# M710H.net
KiCad netlist of a schematic drawn in EAGLE
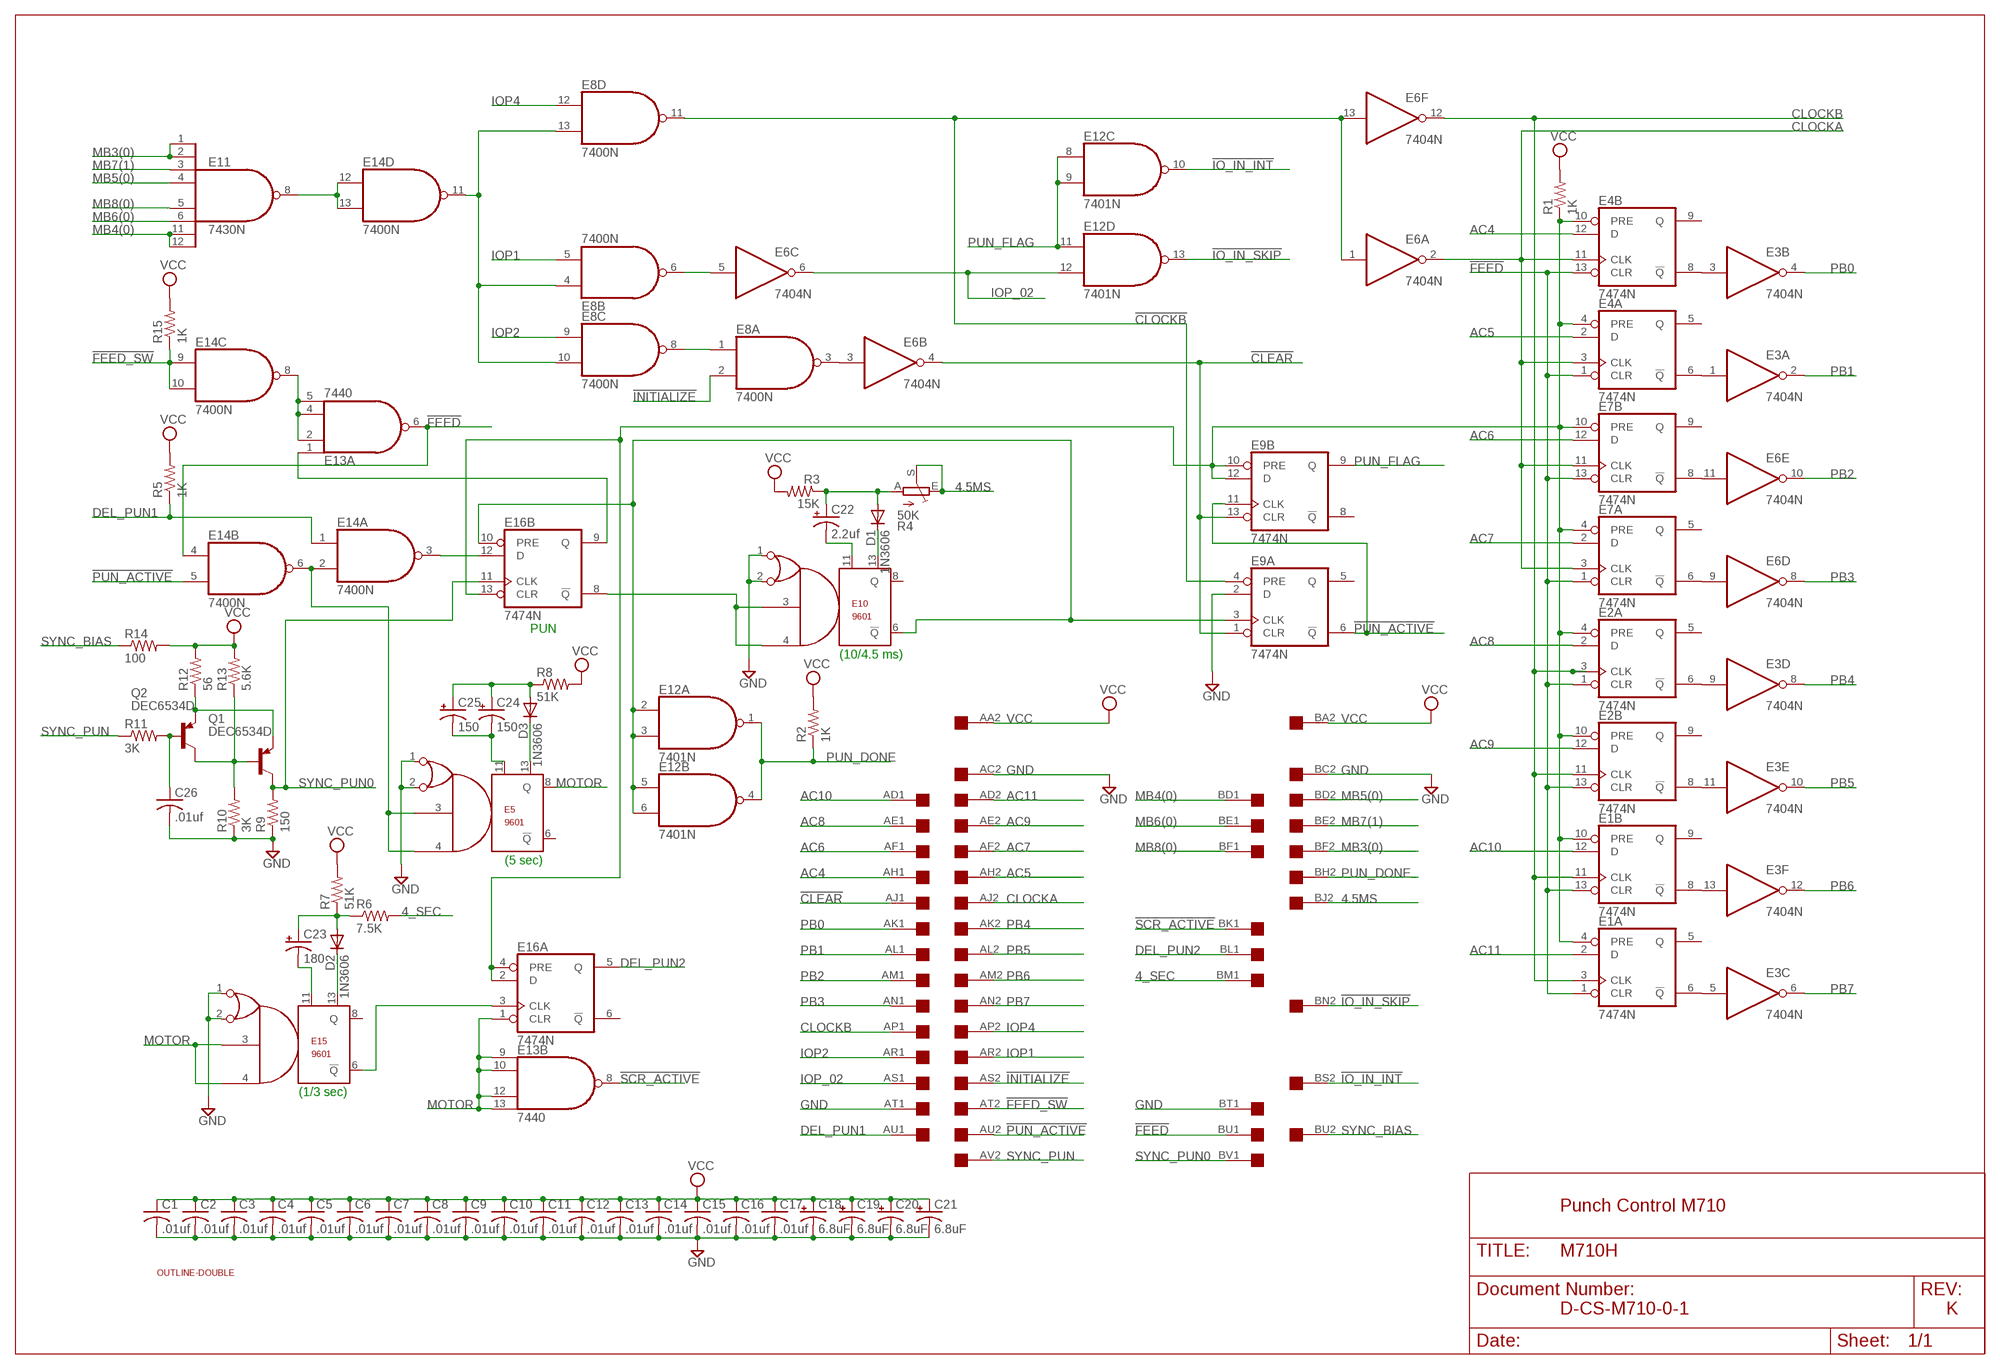
[diagram p0: schematic, sheet 1]

(export (version "E")
  (design (tool "Eeschema 10.0.6"))
  (components
    (comp (ref "C1")
      (value ".01uf")
      (footprint "eagle-import:C050-025X075")
      (libsource (lib "eagle-import") (part "C-US050-025X075"))
    )
    (comp (ref "C2")
      (value ".01uf")
      (footprint "eagle-import:C050-025X075")
      (libsource (lib "eagle-import") (part "C-US050-025X075"))
    )
    (comp (ref "C3")
      (value ".01uf")
      (footprint "eagle-import:C050-025X075")
      (libsource (lib "eagle-import") (part "C-US050-025X075"))
    )
    (comp (ref "C4")
      (value ".01uf")
      (footprint "eagle-import:C050-025X075")
      (libsource (lib "eagle-import") (part "C-US050-025X075"))
    )
    (comp (ref "C5")
      (value ".01uf")
      (footprint "eagle-import:C050-025X075")
      (libsource (lib "eagle-import") (part "C-US050-025X075"))
    )
    (comp (ref "C6")
      (value ".01uf")
      (footprint "eagle-import:C050-025X075")
      (libsource (lib "eagle-import") (part "C-US050-025X075"))
    )
    (comp (ref "C7")
      (value ".01uf")
      (footprint "eagle-import:C050-025X075")
      (libsource (lib "eagle-import") (part "C-US050-025X075"))
    )
    (comp (ref "C8")
      (value ".01uf")
      (footprint "eagle-import:C050-025X075")
      (libsource (lib "eagle-import") (part "C-US050-025X075"))
    )
    (comp (ref "C9")
      (value ".01uf")
      (footprint "eagle-import:C050-025X075")
      (libsource (lib "eagle-import") (part "C-US050-025X075"))
    )
    (comp (ref "C10")
      (value ".01uf")
      (footprint "eagle-import:C050-025X075")
      (libsource (lib "eagle-import") (part "C-US050-025X075"))
    )
    (comp (ref "C11")
      (value ".01uf")
      (footprint "eagle-import:C050-025X075")
      (libsource (lib "eagle-import") (part "C-US050-025X075"))
    )
    (comp (ref "C12")
      (value ".01uf")
      (footprint "eagle-import:C050-025X075")
      (libsource (lib "eagle-import") (part "C-US050-025X075"))
    )
    (comp (ref "C13")
      (value ".01uf")
      (footprint "eagle-import:C050-025X075")
      (libsource (lib "eagle-import") (part "C-US050-025X075"))
    )
    (comp (ref "C14")
      (value ".01uf")
      (footprint "eagle-import:C050-025X075")
      (libsource (lib "eagle-import") (part "C-US050-025X075"))
    )
    (comp (ref "C15")
      (value ".01uf")
      (footprint "eagle-import:C050-025X075")
      (libsource (lib "eagle-import") (part "C-US050-025X075"))
    )
    (comp (ref "C16")
      (value ".01uf")
      (footprint "eagle-import:C050-025X075")
      (libsource (lib "eagle-import") (part "C-US050-025X075"))
    )
    (comp (ref "C17")
      (value ".01uf")
      (footprint "eagle-import:C050-025X075")
      (libsource (lib "eagle-import") (part "C-US050-025X075"))
    )
    (comp (ref "C18")
      (value "6.8uF")
      (footprint "eagle-import:E12-8")
      (libsource (lib "eagle-import") (part "CPOL-USE20-8AXIAL"))
    )
    (comp (ref "C19")
      (value "6.8uF")
      (footprint "eagle-import:E12-8")
      (libsource (lib "eagle-import") (part "CPOL-USE20-8AXIAL"))
    )
    (comp (ref "C20")
      (value "6.8uF")
      (footprint "eagle-import:E12-8")
      (libsource (lib "eagle-import") (part "CPOL-USE20-8AXIAL"))
    )
    (comp (ref "C21")
      (value "6.8uF")
      (footprint "eagle-import:E12-8")
      (libsource (lib "eagle-import") (part "CPOL-USE20-8AXIAL"))
    )
    (comp (ref "C22")
      (value "2.2uf")
      (footprint "eagle-import:E15-5")
      (libsource (lib "eagle-import") (part "CPOL-USE15-5AXIAL"))
    )
    (comp (ref "C23")
      (value "180")
      (footprint "eagle-import:E12-8")
      (libsource (lib "eagle-import") (part "CPOL-USE20-8AXIAL"))
    )
    (comp (ref "C24")
      (value "150")
      (footprint "eagle-import:E22-6")
      (libsource (lib "eagle-import") (part "CPOL-USE22-6AXIAL"))
    )
    (comp (ref "C25")
      (value "150")
      (footprint "eagle-import:E22-6")
      (libsource (lib "eagle-import") (part "CPOL-USE22-6AXIAL"))
    )
    (comp (ref "C26")
      (value ".01uf")
      (footprint "eagle-import:C050-025X075")
      (libsource (lib "eagle-import") (part "C-US050-025X075"))
    )
    (comp (ref "D1")
      (value "1N3606")
      (footprint "eagle-import:DO41-10")
      (libsource (lib "eagle-import") (part "1N4004"))
    )
    (comp (ref "D2")
      (value "1N3606")
      (footprint "eagle-import:DO41-10")
      (libsource (lib "eagle-import") (part "1N4004"))
    )
    (comp (ref "D3")
      (value "1N3606")
      (footprint "eagle-import:DO41-10")
      (libsource (lib "eagle-import") (part "1N4004"))
    )
    (comp (ref "E1")
      (value "7474N")
      (footprint "eagle-import:DIL14")
      (libsource (lib "eagle-import") (part "7474NS"))
    )
    (comp (ref "E2")
      (value "7474N")
      (footprint "eagle-import:DIL14")
      (libsource (lib "eagle-import") (part "7474NS"))
    )
    (comp (ref "E3")
      (value "7404N")
      (footprint "eagle-import:DIL14")
      (libsource (lib "eagle-import") (part "7404N"))
    )
    (comp (ref "E4")
      (value "7474N")
      (footprint "eagle-import:DIL14")
      (libsource (lib "eagle-import") (part "7474NS"))
    )
    (comp (ref "E5")
      (value "9601")
      (footprint "eagle-import:DIL14")
      (libsource (lib "eagle-import") (part "9601"))
    )
    (comp (ref "E6")
      (value "7404N")
      (footprint "eagle-import:DIL14")
      (libsource (lib "eagle-import") (part "7404N"))
    )
    (comp (ref "E7")
      (value "7474N")
      (footprint "eagle-import:DIL14")
      (libsource (lib "eagle-import") (part "7474NS"))
    )
    (comp (ref "E8")
      (value "7400N")
      (footprint "eagle-import:DIL14")
      (libsource (lib "eagle-import") (part "7400N"))
    )
    (comp (ref "E9")
      (value "7474N")
      (footprint "eagle-import:DIL14")
      (libsource (lib "eagle-import") (part "7474NS"))
    )
    (comp (ref "E10")
      (value "9601")
      (footprint "eagle-import:DIL14")
      (libsource (lib "eagle-import") (part "9601"))
    )
    (comp (ref "E11")
      (value "7430N")
      (footprint "eagle-import:DIL14")
      (libsource (lib "eagle-import") (part "7430N"))
    )
    (comp (ref "E12")
      (value "7401N")
      (footprint "eagle-import:DIL14")
      (libsource (lib "eagle-import") (part "7401NLS"))
    )
    (comp (ref "E13")
      (value "7440")
      (footprint "eagle-import:DIL14")
      (libsource (lib "eagle-import") (part "7420NS"))
    )
    (comp (ref "E14")
      (value "7400N")
      (footprint "eagle-import:DIL14")
      (libsource (lib "eagle-import") (part "7400N"))
    )
    (comp (ref "E15")
      (value "9601")
      (footprint "eagle-import:DIL14")
      (libsource (lib "eagle-import") (part "9601"))
    )
    (comp (ref "E16")
      (value "7474N")
      (footprint "eagle-import:DIL14")
      (libsource (lib "eagle-import") (part "7474NS"))
    )
    (comp (ref "Q1")
      (value "DEC6534D")
      (footprint "eagle-import:TO5")
      (libsource (lib "eagle-import") (part "2N2905"))
    )
    (comp (ref "Q2")
      (value "DEC6534D")
      (footprint "eagle-import:TO5")
      (libsource (lib "eagle-import") (part "2N2905"))
    )
    (comp (ref "R1")
      (value "1K")
      (footprint "eagle-import:0207_10")
      (libsource (lib "eagle-import") (part "R-US_0207/10"))
    )
    (comp (ref "R2")
      (value "1K")
      (footprint "eagle-import:0207_10")
      (libsource (lib "eagle-import") (part "R-US_0207/10"))
    )
    (comp (ref "R3")
      (value "15K")
      (footprint "eagle-import:0207_10")
      (libsource (lib "eagle-import") (part "R-US_0207/10"))
    )
    (comp (ref "R4")
      (value "50K")
      (footprint "eagle-import:RJ6")
      (libsource (lib "eagle-import") (part "TRIM_EU-RJ6"))
    )
    (comp (ref "R5")
      (value "1K")
      (footprint "eagle-import:0207_10")
      (libsource (lib "eagle-import") (part "R-US_0207/10"))
    )
    (comp (ref "R6")
      (value "7.5K")
      (footprint "eagle-import:0207_10")
      (libsource (lib "eagle-import") (part "R-US_0207/10"))
    )
    (comp (ref "R7")
      (value "51K")
      (footprint "eagle-import:0207_10")
      (libsource (lib "eagle-import") (part "R-US_0207/10"))
    )
    (comp (ref "R8")
      (value "51K")
      (footprint "eagle-import:0207_10")
      (libsource (lib "eagle-import") (part "R-US_0207/10"))
    )
    (comp (ref "R9")
      (value "150")
      (footprint "eagle-import:0207_10")
      (libsource (lib "eagle-import") (part "R-US_0207/10"))
    )
    (comp (ref "R10")
      (value "3K")
      (footprint "eagle-import:0207_10")
      (libsource (lib "eagle-import") (part "R-US_0207/10"))
    )
    (comp (ref "R11")
      (value "3K")
      (footprint "eagle-import:0207_10")
      (libsource (lib "eagle-import") (part "R-US_0207/10"))
    )
    (comp (ref "R12")
      (value "56")
      (footprint "eagle-import:0207_10")
      (libsource (lib "eagle-import") (part "R-US_0207/10"))
    )
    (comp (ref "R13")
      (value "5.6K")
      (footprint "eagle-import:0207_10")
      (libsource (lib "eagle-import") (part "R-US_0207/10"))
    )
    (comp (ref "R14")
      (value "100")
      (footprint "eagle-import:0207_10")
      (libsource (lib "eagle-import") (part "R-US_0207/10"))
    )
    (comp (ref "R15")
      (value "1K")
      (footprint "eagle-import:0207_10")
      (libsource (lib "eagle-import") (part "R-US_0207/10"))
    )
    (comp (ref "U$1")
      (value "OUTLINE-DOUBLE")
      (footprint "eagle-import:DOUBLE")
      (libsource (lib "eagle-import") (part "OUTLINE-DOUBLE"))
    )
    (comp (ref "U$2")
      (value "DOUBLE")
      (footprint "eagle-import:EDGE-CON4")
      (libsource (lib "eagle-import") (part "DOUBLE"))
    )
  )
  (nets
    (net (code "1") (name "/4.5MS") (class "Default")
      (node (ref "R4") (pin "E") (pinfunction "E_E") (pintype "passive"))
      (node (ref "R4") (pin "S") (pinfunction "S_S") (pintype "passive"))
      (node (ref "U$2") (pin "BJ2") (pinfunction "1_BJ2") (pintype "bidirectional"))
    )
    (net (code "2") (name "/4_SEC") (class "Default")
      (node (ref "R6") (pin "2") (pinfunction "2_2") (pintype "passive"))
      (node (ref "U$2") (pin "BM1") (pinfunction "1_BM1") (pintype "bidirectional"))
    )
    (net (code "3") (name "/AC4") (class "Default")
      (node (ref "E4") (pin "12") (pinfunction "D_12") (pintype "input"))
      (node (ref "U$2") (pin "AH1") (pinfunction "1_AH1") (pintype "bidirectional"))
    )
    (net (code "4") (name "/AC5") (class "Default")
      (node (ref "E4") (pin "2") (pinfunction "D_2") (pintype "input"))
      (node (ref "U$2") (pin "AH2") (pinfunction "1_AH2") (pintype "bidirectional"))
    )
    (net (code "5") (name "/AC6") (class "Default")
      (node (ref "E7") (pin "12") (pinfunction "D_12") (pintype "input"))
      (node (ref "U$2") (pin "AF1") (pinfunction "1_AF1") (pintype "bidirectional"))
    )
    (net (code "6") (name "/AC7") (class "Default")
      (node (ref "E7") (pin "2") (pinfunction "D_2") (pintype "input"))
      (node (ref "U$2") (pin "AF2") (pinfunction "1_AF2") (pintype "bidirectional"))
    )
    (net (code "7") (name "/AC8") (class "Default")
      (node (ref "E2") (pin "2") (pinfunction "D_2") (pintype "input"))
      (node (ref "U$2") (pin "AE1") (pinfunction "1_AE1") (pintype "bidirectional"))
    )
    (net (code "8") (name "/AC9") (class "Default")
      (node (ref "E2") (pin "12") (pinfunction "D_12") (pintype "input"))
      (node (ref "U$2") (pin "AE2") (pinfunction "1_AE2") (pintype "bidirectional"))
    )
    (net (code "9") (name "/AC10") (class "Default")
      (node (ref "E1") (pin "12") (pinfunction "D_12") (pintype "input"))
      (node (ref "U$2") (pin "AD1") (pinfunction "1_AD1") (pintype "bidirectional"))
    )
    (net (code "10") (name "/AC11") (class "Default")
      (node (ref "E1") (pin "2") (pinfunction "D_2") (pintype "input"))
      (node (ref "U$2") (pin "AD2") (pinfunction "1_AD2") (pintype "bidirectional"))
    )
    (net (code "11") (name "/CLOCKA") (class "Default")
      (node (ref "E4") (pin "11") (pinfunction "CLK_11") (pintype "input"))
      (node (ref "E4") (pin "3") (pinfunction "CLK_3") (pintype "input"))
      (node (ref "E6") (pin "2") (pinfunction "O_2") (pintype "output"))
      (node (ref "E7") (pin "11") (pinfunction "CLK_11") (pintype "input"))
      (node (ref "E7") (pin "3") (pinfunction "CLK_3") (pintype "input"))
      (node (ref "U$2") (pin "AJ2") (pinfunction "1_AJ2") (pintype "bidirectional"))
    )
    (net (code "12") (name "/CLOCKB") (class "Default")
      (node (ref "E1") (pin "11") (pinfunction "CLK_11") (pintype "input"))
      (node (ref "E1") (pin "3") (pinfunction "CLK_3") (pintype "input"))
      (node (ref "E2") (pin "11") (pinfunction "CLK_11") (pintype "input"))
      (node (ref "E2") (pin "3") (pinfunction "CLK_3") (pintype "input"))
      (node (ref "E6") (pin "12") (pinfunction "O_12") (pintype "output"))
      (node (ref "U$2") (pin "AP1") (pinfunction "1_AP1") (pintype "bidirectional"))
    )
    (net (code "13") (name "/DEL_PUN1") (class "Default")
      (node (ref "E14") (pin "1") (pinfunction "I0_1") (pintype "input"))
      (node (ref "R5") (pin "1") (pinfunction "1_1") (pintype "passive"))
      (node (ref "U$2") (pin "AU1") (pinfunction "1_AU1") (pintype "bidirectional"))
    )
    (net (code "14") (name "/DEL_PUN2") (class "Default")
      (node (ref "E16") (pin "5") (pinfunction "Q_5") (pintype "output"))
      (node (ref "U$2") (pin "BL1") (pinfunction "1_BL1") (pintype "bidirectional"))
    )
    (net (code "15") (name "/IOP1") (class "Default")
      (node (ref "E8") (pin "5") (pinfunction "I1_5") (pintype "input"))
      (node (ref "U$2") (pin "AR2") (pinfunction "1_AR2") (pintype "bidirectional"))
    )
    (net (code "16") (name "/IOP2") (class "Default")
      (node (ref "E8") (pin "9") (pinfunction "I0_9") (pintype "input"))
      (node (ref "U$2") (pin "AR1") (pinfunction "1_AR1") (pintype "bidirectional"))
    )
    (net (code "17") (name "/IOP4") (class "Default")
      (node (ref "E8") (pin "12") (pinfunction "I0_12") (pintype "input"))
      (node (ref "U$2") (pin "AP2") (pinfunction "1_AP2") (pintype "bidirectional"))
    )
    (net (code "18") (name "/IOP_02") (class "Default")
      (node (ref "E12") (pin "12") (pinfunction "I1_12") (pintype "input"))
      (node (ref "E6") (pin "6") (pinfunction "O_6") (pintype "output"))
      (node (ref "U$2") (pin "AS1") (pinfunction "1_AS1") (pintype "bidirectional"))
    )
    (net (code "19") (name "/MB3(0)") (class "Default")
      (node (ref "E11") (pin "1") (pinfunction "I0_1") (pintype "input"))
      (node (ref "E11") (pin "2") (pinfunction "I1_2") (pintype "input"))
      (node (ref "U$2") (pin "BF2") (pinfunction "1_BF2") (pintype "bidirectional"))
    )
    (net (code "20") (name "/MB4(0)") (class "Default")
      (node (ref "E11") (pin "11") (pinfunction "I6_11") (pintype "input"))
      (node (ref "E11") (pin "12") (pinfunction "I7_12") (pintype "input"))
      (node (ref "U$2") (pin "BD1") (pinfunction "1_BD1") (pintype "bidirectional"))
    )
    (net (code "21") (name "/MB5(0)") (class "Default")
      (node (ref "E11") (pin "4") (pinfunction "I3_4") (pintype "input"))
      (node (ref "U$2") (pin "BD2") (pinfunction "1_BD2") (pintype "bidirectional"))
    )
    (net (code "22") (name "/MB6(0)") (class "Default")
      (node (ref "E11") (pin "6") (pinfunction "I5_6") (pintype "input"))
      (node (ref "U$2") (pin "BE1") (pinfunction "1_BE1") (pintype "bidirectional"))
    )
    (net (code "23") (name "/MB7(1)") (class "Default")
      (node (ref "E11") (pin "3") (pinfunction "I2_3") (pintype "input"))
      (node (ref "U$2") (pin "BE2") (pinfunction "1_BE2") (pintype "bidirectional"))
    )
    (net (code "24") (name "/MB8(0)") (class "Default")
      (node (ref "E11") (pin "5") (pinfunction "I4_5") (pintype "input"))
      (node (ref "U$2") (pin "BF1") (pinfunction "1_BF1") (pintype "bidirectional"))
    )
    (net (code "25") (name "/MOTOR") (class "Default")
      (node (ref "E13") (pin "10") (pinfunction "I1_10") (pintype "input"))
      (node (ref "E13") (pin "12") (pinfunction "I2_12") (pintype "input"))
      (node (ref "E13") (pin "13") (pinfunction "I3_13") (pintype "input"))
      (node (ref "E13") (pin "9") (pinfunction "I0_9") (pintype "input"))
      (node (ref "E15") (pin "3") (pinfunction "P$3_3") (pintype "input"))
      (node (ref "E15") (pin "4") (pinfunction "P$4_4") (pintype "input"))
      (node (ref "E16") (pin "1") (pinfunction "CLR_1") (pintype "input"))
      (node (ref "E5") (pin "8") (pinfunction "Q_8") (pintype "output"))
    )
    (net (code "26") (name "/PB0") (class "Default")
      (node (ref "E3") (pin "4") (pinfunction "O_4") (pintype "output"))
      (node (ref "U$2") (pin "AK1") (pinfunction "1_AK1") (pintype "bidirectional"))
    )
    (net (code "27") (name "/PB1") (class "Default")
      (node (ref "E3") (pin "2") (pinfunction "O_2") (pintype "output"))
      (node (ref "U$2") (pin "AL1") (pinfunction "1_AL1") (pintype "bidirectional"))
    )
    (net (code "28") (name "/PB2") (class "Default")
      (node (ref "E6") (pin "10") (pinfunction "O_10") (pintype "output"))
      (node (ref "U$2") (pin "AM1") (pinfunction "1_AM1") (pintype "bidirectional"))
    )
    (net (code "29") (name "/PB3") (class "Default")
      (node (ref "E6") (pin "8") (pinfunction "O_8") (pintype "output"))
      (node (ref "U$2") (pin "AN1") (pinfunction "1_AN1") (pintype "bidirectional"))
    )
    (net (code "30") (name "/PB4") (class "Default")
      (node (ref "E3") (pin "8") (pinfunction "O_8") (pintype "output"))
      (node (ref "U$2") (pin "AK2") (pinfunction "1_AK2") (pintype "bidirectional"))
    )
    (net (code "31") (name "/PB5") (class "Default")
      (node (ref "E3") (pin "10") (pinfunction "O_10") (pintype "output"))
      (node (ref "U$2") (pin "AL2") (pinfunction "1_AL2") (pintype "bidirectional"))
    )
    (net (code "32") (name "/PB6") (class "Default")
      (node (ref "E3") (pin "12") (pinfunction "O_12") (pintype "output"))
      (node (ref "U$2") (pin "AM2") (pinfunction "1_AM2") (pintype "bidirectional"))
    )
    (net (code "33") (name "/PB7") (class "Default")
      (node (ref "E3") (pin "6") (pinfunction "O_6") (pintype "output"))
      (node (ref "U$2") (pin "AN2") (pinfunction "1_AN2") (pintype "bidirectional"))
    )
    (net (code "34") (name "/PUN_DONE") (class "Default")
      (node (ref "E12") (pin "1") (pinfunction "O_1") (pintype "open_collector"))
      (node (ref "E12") (pin "4") (pinfunction "O_4") (pintype "open_collector"))
      (node (ref "R2") (pin "1") (pinfunction "1_1") (pintype "passive"))
      (node (ref "U$2") (pin "BH2") (pinfunction "1_BH2") (pintype "bidirectional"))
    )
    (net (code "35") (name "/PUN_FLAG") (class "Default")
      (node (ref "E12") (pin "11") (pinfunction "I0_11") (pintype "input"))
      (node (ref "E12") (pin "8") (pinfunction "I0_8") (pintype "input"))
      (node (ref "E12") (pin "9") (pinfunction "I1_9") (pintype "input"))
      (node (ref "E9") (pin "9") (pinfunction "Q_9") (pintype "output"))
    )
    (net (code "36") (name "/SYNC_BIAS") (class "Default")
      (node (ref "R14") (pin "1") (pinfunction "1_1") (pintype "passive"))
      (node (ref "U$2") (pin "BU2") (pinfunction "1_BU2") (pintype "bidirectional"))
    )
    (net (code "37") (name "/SYNC_PUN") (class "Default")
      (node (ref "R11") (pin "1") (pinfunction "1_1") (pintype "passive"))
      (node (ref "U$2") (pin "AV2") (pinfunction "1_AV2") (pintype "bidirectional"))
    )
    (net (code "38") (name "/SYNC_PUN0") (class "Default")
      (node (ref "E16") (pin "11") (pinfunction "CLK_11") (pintype "input"))
      (node (ref "Q1") (pin "3") (pinfunction "C_3") (pintype "passive"))
      (node (ref "R9") (pin "2") (pinfunction "2_2") (pintype "passive"))
      (node (ref "U$2") (pin "BV1") (pinfunction "1_BV1") (pintype "bidirectional"))
    )
    (net (code "39") (name "/~{CLEAR}") (class "Default")
      (node (ref "E6") (pin "4") (pinfunction "O_4") (pintype "output"))
      (node (ref "E9") (pin "1") (pinfunction "CLR_1") (pintype "input"))
      (node (ref "E9") (pin "13") (pinfunction "CLR_13") (pintype "input"))
      (node (ref "U$2") (pin "AJ1") (pinfunction "1_AJ1") (pintype "bidirectional"))
    )
    (net (code "40") (name "/~{CLOCKB}") (class "Default")
      (node (ref "E6") (pin "1") (pinfunction "I_1") (pintype "input"))
      (node (ref "E6") (pin "13") (pinfunction "I_13") (pintype "input"))
      (node (ref "E8") (pin "11") (pinfunction "O_11") (pintype "output"))
      (node (ref "E9") (pin "4") (pinfunction "PRE_4") (pintype "input"))
    )
    (net (code "41") (name "/~{FEED_SW}") (class "Default")
      (node (ref "E14") (pin "10") (pinfunction "I1_10") (pintype "input"))
      (node (ref "E14") (pin "9") (pinfunction "I0_9") (pintype "input"))
      (node (ref "R15") (pin "1") (pinfunction "1_1") (pintype "passive"))
      (node (ref "U$2") (pin "AT2") (pinfunction "1_AT2") (pintype "bidirectional"))
    )
    (net (code "42") (name "/~{FEED}") (class "Default")
      (node (ref "E1") (pin "1") (pinfunction "CLR_1") (pintype "input"))
      (node (ref "E1") (pin "13") (pinfunction "CLR_13") (pintype "input"))
      (node (ref "E13") (pin "6") (pinfunction "O_6") (pintype "output"))
      (node (ref "E14") (pin "4") (pinfunction "I0_4") (pintype "input"))
      (node (ref "E2") (pin "1") (pinfunction "CLR_1") (pintype "input"))
      (node (ref "E2") (pin "13") (pinfunction "CLR_13") (pintype "input"))
      (node (ref "E4") (pin "1") (pinfunction "CLR_1") (pintype "input"))
      (node (ref "E4") (pin "13") (pinfunction "CLR_13") (pintype "input"))
      (node (ref "E7") (pin "1") (pinfunction "CLR_1") (pintype "input"))
      (node (ref "E7") (pin "13") (pinfunction "CLR_13") (pintype "input"))
      (node (ref "U$2") (pin "BU1") (pinfunction "1_BU1") (pintype "bidirectional"))
    )
    (net (code "43") (name "/~{INITIALIZE}") (class "Default")
      (node (ref "E8") (pin "2") (pinfunction "I1_2") (pintype "input"))
      (node (ref "U$2") (pin "AS2") (pinfunction "1_AS2") (pintype "bidirectional"))
    )
    (net (code "44") (name "/~{IO_IN_INT}") (class "Default")
      (node (ref "E12") (pin "10") (pinfunction "O_10") (pintype "open_collector"))
      (node (ref "U$2") (pin "BS2") (pinfunction "1_BS2") (pintype "bidirectional"))
    )
    (net (code "45") (name "/~{IO_IN_SKIP}") (class "Default")
      (node (ref "E12") (pin "13") (pinfunction "O_13") (pintype "open_collector"))
      (node (ref "U$2") (pin "BN2") (pinfunction "1_BN2") (pintype "bidirectional"))
    )
    (net (code "46") (name "/~{PUN_ACTIVE}") (class "Default")
      (node (ref "E14") (pin "5") (pinfunction "I1_5") (pintype "input"))
      (node (ref "E9") (pin "11") (pinfunction "CLK_11") (pintype "input"))
      (node (ref "E9") (pin "6") (pinfunction "~{Q}_6") (pintype "output"))
      (node (ref "U$2") (pin "AU2") (pinfunction "1_AU2") (pintype "bidirectional"))
    )
    (net (code "47") (name "/~{SCR_ACTIVE}") (class "Default")
      (node (ref "E13") (pin "8") (pinfunction "O_8") (pintype "output"))
      (node (ref "U$2") (pin "BK1") (pinfunction "1_BK1") (pintype "bidirectional"))
    )
    (net (code "48") (name "GND") (class "Default")
      (node (ref "C1") (pin "2") (pinfunction "2_2") (pintype "passive"))
      (node (ref "C10") (pin "2") (pinfunction "2_2") (pintype "passive"))
      (node (ref "C11") (pin "2") (pinfunction "2_2") (pintype "passive"))
      (node (ref "C12") (pin "2") (pinfunction "2_2") (pintype "passive"))
      (node (ref "C13") (pin "2") (pinfunction "2_2") (pintype "passive"))
      (node (ref "C14") (pin "2") (pinfunction "2_2") (pintype "passive"))
      (node (ref "C15") (pin "2") (pinfunction "2_2") (pintype "passive"))
      (node (ref "C16") (pin "2") (pinfunction "2_2") (pintype "passive"))
      (node (ref "C17") (pin "2") (pinfunction "2_2") (pintype "passive"))
      (node (ref "C18") (pin "-") (pinfunction "-_-") (pintype "passive"))
      (node (ref "C19") (pin "-") (pinfunction "-_-") (pintype "passive"))
      (node (ref "C2") (pin "2") (pinfunction "2_2") (pintype "passive"))
      (node (ref "C20") (pin "-") (pinfunction "-_-") (pintype "passive"))
      (node (ref "C21") (pin "-") (pinfunction "-_-") (pintype "passive"))
      (node (ref "C26") (pin "2") (pinfunction "2_2") (pintype "passive"))
      (node (ref "C3") (pin "2") (pinfunction "2_2") (pintype "passive"))
      (node (ref "C4") (pin "2") (pinfunction "2_2") (pintype "passive"))
      (node (ref "C5") (pin "2") (pinfunction "2_2") (pintype "passive"))
      (node (ref "C6") (pin "2") (pinfunction "2_2") (pintype "passive"))
      (node (ref "C7") (pin "2") (pinfunction "2_2") (pintype "passive"))
      (node (ref "C8") (pin "2") (pinfunction "2_2") (pintype "passive"))
      (node (ref "C9") (pin "2") (pinfunction "2_2") (pintype "passive"))
      (node (ref "E10") (pin "1") (pinfunction "P$1_1") (pintype "input"))
      (node (ref "E10") (pin "2") (pinfunction "P$2_2") (pintype "input"))
      (node (ref "E15") (pin "1") (pinfunction "P$1_1") (pintype "input"))
      (node (ref "E15") (pin "2") (pinfunction "P$2_2") (pintype "input"))
      (node (ref "E5") (pin "1") (pinfunction "P$1_1") (pintype "input"))
      (node (ref "E5") (pin "2") (pinfunction "P$2_2") (pintype "input"))
      (node (ref "E9") (pin "2") (pinfunction "D_2") (pintype "input"))
      (node (ref "R10") (pin "1") (pinfunction "1_1") (pintype "passive"))
      (node (ref "R9") (pin "1") (pinfunction "1_1") (pintype "passive"))
      (node (ref "U$2") (pin "AC2") (pinfunction "1_AC2") (pintype "bidirectional"))
      (node (ref "U$2") (pin "AT1") (pinfunction "1_AT1") (pintype "bidirectional"))
      (node (ref "U$2") (pin "BC2") (pinfunction "1_BC2") (pintype "bidirectional"))
      (node (ref "U$2") (pin "BT1") (pinfunction "1_BT1") (pintype "bidirectional"))
    )
    (net (code "49") (name "Net-(C22-Pad+)") (class "Default")
      (node (ref "C22") (pin "+") (pinfunction "+_+") (pintype "passive"))
      (node (ref "D1") (pin "A") (pinfunction "A_A") (pintype "passive"))
      (node (ref "R3") (pin "1") (pinfunction "1_1") (pintype "passive"))
      (node (ref "R4") (pin "A") (pinfunction "A_A") (pintype "passive"))
    )
    (net (code "50") (name "Net-(C23-Pad+)") (class "Default")
      (node (ref "C23") (pin "+") (pinfunction "+_+") (pintype "passive"))
      (node (ref "D2") (pin "A") (pinfunction "A_A") (pintype "passive"))
      (node (ref "R6") (pin "1") (pinfunction "1_1") (pintype "passive"))
      (node (ref "R7") (pin "1") (pinfunction "1_1") (pintype "passive"))
    )
    (net (code "51") (name "Net-(C24-Pad+)") (class "Default")
      (node (ref "C24") (pin "+") (pinfunction "+_+") (pintype "passive"))
      (node (ref "C25") (pin "+") (pinfunction "+_+") (pintype "passive"))
      (node (ref "D3") (pin "A") (pinfunction "A_A") (pintype "passive"))
      (node (ref "R8") (pin "1") (pinfunction "1_1") (pintype "passive"))
    )
    (net (code "52") (name "Net-(E1A-~{Q})") (class "Default")
      (node (ref "E1") (pin "6") (pinfunction "~{Q}_6") (pintype "output"))
      (node (ref "E3") (pin "5") (pinfunction "I_5") (pintype "input"))
    )
    (net (code "53") (name "Net-(E1B-~{Q})") (class "Default")
      (node (ref "E1") (pin "8") (pinfunction "~{Q}_8") (pintype "output"))
      (node (ref "E3") (pin "13") (pinfunction "I_13") (pintype "input"))
    )
    (net (code "54") (name "Net-(E2A-~{Q})") (class "Default")
      (node (ref "E2") (pin "6") (pinfunction "~{Q}_6") (pintype "output"))
      (node (ref "E3") (pin "9") (pinfunction "I_9") (pintype "input"))
    )
    (net (code "55") (name "Net-(E2B-~{Q})") (class "Default")
      (node (ref "E2") (pin "8") (pinfunction "~{Q}_8") (pintype "output"))
      (node (ref "E3") (pin "11") (pinfunction "I_11") (pintype "input"))
    )
    (net (code "56") (name "Net-(E3A-I)") (class "Default")
      (node (ref "E3") (pin "1") (pinfunction "I_1") (pintype "input"))
      (node (ref "E4") (pin "6") (pinfunction "~{Q}_6") (pintype "output"))
    )
    (net (code "57") (name "Net-(E3B-I)") (class "Default")
      (node (ref "E3") (pin "3") (pinfunction "I_3") (pintype "input"))
      (node (ref "E4") (pin "8") (pinfunction "~{Q}_8") (pintype "output"))
    )
    (net (code "58") (name "Net-(E5A-P$5)") (class "Default")
      (node (ref "C24") (pin "-") (pinfunction "-_-") (pintype "passive"))
      (node (ref "C25") (pin "-") (pinfunction "-_-") (pintype "passive"))
      (node (ref "E5") (pin "11") (pinfunction "P$5_11") (pintype "bidirectional"))
    )
    (net (code "59") (name "Net-(E5A-P$6)") (class "Default")
      (node (ref "D3") (pin "C") (pinfunction "C_C") (pintype "passive"))
      (node (ref "E5") (pin "13") (pinfunction "P$6_13") (pintype "bidirectional"))
    )
    (net (code "60") (name "Net-(E6B-I)") (class "Default")
      (node (ref "E6") (pin "3") (pinfunction "I_3") (pintype "input"))
      (node (ref "E8") (pin "3") (pinfunction "O_3") (pintype "output"))
    )
    (net (code "61") (name "Net-(E6C-I)") (class "Default")
      (node (ref "E6") (pin "5") (pinfunction "I_5") (pintype "input"))
      (node (ref "E8") (pin "6") (pinfunction "O_6") (pintype "output"))
    )
    (net (code "62") (name "Net-(E6D-I)") (class "Default")
      (node (ref "E6") (pin "9") (pinfunction "I_9") (pintype "input"))
      (node (ref "E7") (pin "6") (pinfunction "~{Q}_6") (pintype "output"))
    )
    (net (code "63") (name "Net-(E6E-I)") (class "Default")
      (node (ref "E6") (pin "11") (pinfunction "I_11") (pintype "input"))
      (node (ref "E7") (pin "8") (pinfunction "~{Q}_8") (pintype "output"))
    )
    (net (code "64") (name "Net-(E8A-I0)") (class "Default")
      (node (ref "E8") (pin "1") (pinfunction "I0_1") (pintype "input"))
      (node (ref "E8") (pin "8") (pinfunction "O_8") (pintype "output"))
    )
    (net (code "65") (name "Net-(E10A-P$3)") (class "Default")
      (node (ref "E10") (pin "3") (pinfunction "P$3_3") (pintype "input"))
      (node (ref "E10") (pin "4") (pinfunction "P$4_4") (pintype "input"))
      (node (ref "E16") (pin "8") (pinfunction "~{Q}_8") (pintype "output"))
    )
    (net (code "66") (name "Net-(E10A-P$5)") (class "Default")
      (node (ref "C22") (pin "-") (pinfunction "-_-") (pintype "passive"))
      (node (ref "E10") (pin "11") (pinfunction "P$5_11") (pintype "bidirectional"))
    )
    (net (code "67") (name "Net-(E10A-P$6)") (class "Default")
      (node (ref "D1") (pin "C") (pinfunction "C_C") (pintype "passive"))
      (node (ref "E10") (pin "13") (pinfunction "P$6_13") (pintype "bidirectional"))
    )
    (net (code "68") (name "Net-(E10A-~{Q})") (class "Default")
      (node (ref "E10") (pin "6") (pinfunction "~{Q}_6") (pintype "output"))
      (node (ref "E12") (pin "2") (pinfunction "I0_2") (pintype "input"))
      (node (ref "E12") (pin "3") (pinfunction "I1_3") (pintype "input"))
      (node (ref "E12") (pin "5") (pinfunction "I0_5") (pintype "input"))
      (node (ref "E12") (pin "6") (pinfunction "I1_6") (pintype "input"))
      (node (ref "E16") (pin "10") (pinfunction "PRE_10") (pintype "input"))
      (node (ref "E9") (pin "3") (pinfunction "CLK_3") (pintype "input"))
    )
    (net (code "69") (name "Net-(E11A-O)") (class "Default")
      (node (ref "E11") (pin "8") (pinfunction "O_8") (pintype "output"))
      (node (ref "E14") (pin "12") (pinfunction "I0_12") (pintype "input"))
      (node (ref "E14") (pin "13") (pinfunction "I1_13") (pintype "input"))
    )
    (net (code "70") (name "Net-(E13A-I0)") (class "Default")
      (node (ref "E13") (pin "1") (pinfunction "I0_1") (pintype "input"))
      (node (ref "E16") (pin "9") (pinfunction "Q_9") (pintype "output"))
    )
    (net (code "71") (name "Net-(E13A-I1)") (class "Default")
      (node (ref "E13") (pin "2") (pinfunction "I1_2") (pintype "input"))
      (node (ref "E13") (pin "4") (pinfunction "I2_4") (pintype "input"))
      (node (ref "E13") (pin "5") (pinfunction "I3_5") (pintype "input"))
      (node (ref "E14") (pin "8") (pinfunction "O_8") (pintype "output"))
    )
    (net (code "72") (name "Net-(E14A-I1)") (class "Default")
      (node (ref "E14") (pin "2") (pinfunction "I1_2") (pintype "input"))
      (node (ref "E14") (pin "6") (pinfunction "O_6") (pintype "output"))
      (node (ref "E5") (pin "3") (pinfunction "P$3_3") (pintype "input"))
      (node (ref "E5") (pin "4") (pinfunction "P$4_4") (pintype "input"))
    )
    (net (code "73") (name "Net-(E14A-O)") (class "Default")
      (node (ref "E14") (pin "3") (pinfunction "O_3") (pintype "output"))
      (node (ref "E16") (pin "12") (pinfunction "D_12") (pintype "input"))
    )
    (net (code "74") (name "Net-(E14D-O)") (class "Default")
      (node (ref "E14") (pin "11") (pinfunction "O_11") (pintype "output"))
      (node (ref "E8") (pin "10") (pinfunction "I1_10") (pintype "input"))
      (node (ref "E8") (pin "13") (pinfunction "I1_13") (pintype "input"))
      (node (ref "E8") (pin "4") (pinfunction "I0_4") (pintype "input"))
    )
    (net (code "75") (name "Net-(E15A-P$5)") (class "Default")
      (node (ref "C23") (pin "-") (pinfunction "-_-") (pintype "passive"))
      (node (ref "E15") (pin "11") (pinfunction "P$5_11") (pintype "bidirectional"))
    )
    (net (code "76") (name "Net-(E15A-P$6)") (class "Default")
      (node (ref "D2") (pin "C") (pinfunction "C_C") (pintype "passive"))
      (node (ref "E15") (pin "13") (pinfunction "P$6_13") (pintype "bidirectional"))
    )
    (net (code "77") (name "Net-(E15A-~{Q})") (class "Default")
      (node (ref "E15") (pin "6") (pinfunction "~{Q}_6") (pintype "output"))
      (node (ref "E16") (pin "3") (pinfunction "CLK_3") (pintype "input"))
    )
    (net (code "78") (name "Net-(E16A-D)") (class "Default")
      (node (ref "E1") (pin "10") (pinfunction "PRE_10") (pintype "input"))
      (node (ref "E1") (pin "4") (pinfunction "PRE_4") (pintype "input"))
      (node (ref "E16") (pin "13") (pinfunction "CLR_13") (pintype "input"))
      (node (ref "E16") (pin "2") (pinfunction "D_2") (pintype "input"))
      (node (ref "E16") (pin "4") (pinfunction "PRE_4") (pintype "input"))
      (node (ref "E2") (pin "10") (pinfunction "PRE_10") (pintype "input"))
      (node (ref "E2") (pin "4") (pinfunction "PRE_4") (pintype "input"))
      (node (ref "E4") (pin "10") (pinfunction "PRE_10") (pintype "input"))
      (node (ref "E4") (pin "4") (pinfunction "PRE_4") (pintype "input"))
      (node (ref "E7") (pin "10") (pinfunction "PRE_10") (pintype "input"))
      (node (ref "E7") (pin "4") (pinfunction "PRE_4") (pintype "input"))
      (node (ref "E9") (pin "10") (pinfunction "PRE_10") (pintype "input"))
      (node (ref "E9") (pin "12") (pinfunction "D_12") (pintype "input"))
      (node (ref "R1") (pin "1") (pinfunction "1_1") (pintype "passive"))
    )
    (net (code "79") (name "Net-(Q1-B)") (class "Default")
      (node (ref "Q1") (pin "2") (pinfunction "B_2") (pintype "passive"))
      (node (ref "Q2") (pin "3") (pinfunction "C_3") (pintype "passive"))
      (node (ref "R10") (pin "2") (pinfunction "2_2") (pintype "passive"))
      (node (ref "R13") (pin "1") (pinfunction "1_1") (pintype "passive"))
    )
    (net (code "80") (name "Net-(Q1-E)") (class "Default")
      (node (ref "Q1") (pin "1") (pinfunction "E_1") (pintype "passive"))
      (node (ref "Q2") (pin "1") (pinfunction "E_1") (pintype "passive"))
      (node (ref "R12") (pin "1") (pinfunction "1_1") (pintype "passive"))
    )
    (net (code "81") (name "Net-(Q2-B)") (class "Default")
      (node (ref "C26") (pin "1") (pinfunction "1_1") (pintype "passive"))
      (node (ref "Q2") (pin "2") (pinfunction "B_2") (pintype "passive"))
      (node (ref "R11") (pin "2") (pinfunction "2_2") (pintype "passive"))
    )
    (net (code "82") (name "VCC") (class "Default")
      (node (ref "C1") (pin "1") (pinfunction "1_1") (pintype "passive"))
      (node (ref "C10") (pin "1") (pinfunction "1_1") (pintype "passive"))
      (node (ref "C11") (pin "1") (pinfunction "1_1") (pintype "passive"))
      (node (ref "C12") (pin "1") (pinfunction "1_1") (pintype "passive"))
      (node (ref "C13") (pin "1") (pinfunction "1_1") (pintype "passive"))
      (node (ref "C14") (pin "1") (pinfunction "1_1") (pintype "passive"))
      (node (ref "C15") (pin "1") (pinfunction "1_1") (pintype "passive"))
      (node (ref "C16") (pin "1") (pinfunction "1_1") (pintype "passive"))
      (node (ref "C17") (pin "1") (pinfunction "1_1") (pintype "passive"))
      (node (ref "C18") (pin "+") (pinfunction "+_+") (pintype "passive"))
      (node (ref "C19") (pin "+") (pinfunction "+_+") (pintype "passive"))
      (node (ref "C2") (pin "1") (pinfunction "1_1") (pintype "passive"))
      (node (ref "C20") (pin "+") (pinfunction "+_+") (pintype "passive"))
      (node (ref "C21") (pin "+") (pinfunction "+_+") (pintype "passive"))
      (node (ref "C3") (pin "1") (pinfunction "1_1") (pintype "passive"))
      (node (ref "C4") (pin "1") (pinfunction "1_1") (pintype "passive"))
      (node (ref "C5") (pin "1") (pinfunction "1_1") (pintype "passive"))
      (node (ref "C6") (pin "1") (pinfunction "1_1") (pintype "passive"))
      (node (ref "C7") (pin "1") (pinfunction "1_1") (pintype "passive"))
      (node (ref "C8") (pin "1") (pinfunction "1_1") (pintype "passive"))
      (node (ref "C9") (pin "1") (pinfunction "1_1") (pintype "passive"))
      (node (ref "R1") (pin "2") (pinfunction "2_2") (pintype "passive"))
      (node (ref "R12") (pin "2") (pinfunction "2_2") (pintype "passive"))
      (node (ref "R13") (pin "2") (pinfunction "2_2") (pintype "passive"))
      (node (ref "R14") (pin "2") (pinfunction "2_2") (pintype "passive"))
      (node (ref "R15") (pin "2") (pinfunction "2_2") (pintype "passive"))
      (node (ref "R2") (pin "2") (pinfunction "2_2") (pintype "passive"))
      (node (ref "R3") (pin "2") (pinfunction "2_2") (pintype "passive"))
      (node (ref "R5") (pin "2") (pinfunction "2_2") (pintype "passive"))
      (node (ref "R7") (pin "2") (pinfunction "2_2") (pintype "passive"))
      (node (ref "R8") (pin "2") (pinfunction "2_2") (pintype "passive"))
      (node (ref "U$2") (pin "AA2") (pinfunction "1_AA2") (pintype "bidirectional"))
      (node (ref "U$2") (pin "BA2") (pinfunction "1_BA2") (pintype "bidirectional"))
    )
    (net (code "83") (name "unconnected-(E1A-Q-Pad5)") (class "Default")
      (node (ref "E1") (pin "5") (pinfunction "Q_5") (pintype "output"))
    )
    (net (code "84") (name "unconnected-(E1B-Q-Pad9)") (class "Default")
      (node (ref "E1") (pin "9") (pinfunction "Q_9") (pintype "output"))
    )
    (net (code "85") (name "unconnected-(E2A-Q-Pad5)") (class "Default")
      (node (ref "E2") (pin "5") (pinfunction "Q_5") (pintype "output"))
    )
    (net (code "86") (name "unconnected-(E2B-Q-Pad9)") (class "Default")
      (node (ref "E2") (pin "9") (pinfunction "Q_9") (pintype "output"))
    )
    (net (code "87") (name "unconnected-(E4A-Q-Pad5)") (class "Default")
      (node (ref "E4") (pin "5") (pinfunction "Q_5") (pintype "output"))
    )
    (net (code "88") (name "unconnected-(E4B-Q-Pad9)") (class "Default")
      (node (ref "E4") (pin "9") (pinfunction "Q_9") (pintype "output"))
    )
    (net (code "89") (name "unconnected-(E5A-~{Q}-Pad6)") (class "Default")
      (node (ref "E5") (pin "6") (pinfunction "~{Q}_6") (pintype "output"))
    )
    (net (code "90") (name "unconnected-(E7A-Q-Pad5)") (class "Default")
      (node (ref "E7") (pin "5") (pinfunction "Q_5") (pintype "output"))
    )
    (net (code "91") (name "unconnected-(E7B-Q-Pad9)") (class "Default")
      (node (ref "E7") (pin "9") (pinfunction "Q_9") (pintype "output"))
    )
    (net (code "92") (name "unconnected-(E9A-Q-Pad5)") (class "Default")
      (node (ref "E9") (pin "5") (pinfunction "Q_5") (pintype "output"))
    )
    (net (code "93") (name "unconnected-(E9B-~{Q}-Pad8)") (class "Default")
      (node (ref "E9") (pin "8") (pinfunction "~{Q}_8") (pintype "output"))
    )
    (net (code "94") (name "unconnected-(E10A-Q-Pad8)") (class "Default")
      (node (ref "E10") (pin "8") (pinfunction "Q_8") (pintype "output"))
    )
    (net (code "95") (name "unconnected-(E15A-Q-Pad8)") (class "Default")
      (node (ref "E15") (pin "8") (pinfunction "Q_8") (pintype "output"))
    )
    (net (code "96") (name "unconnected-(E16A-~{Q}-Pad6)") (class "Default")
      (node (ref "E16") (pin "6") (pinfunction "~{Q}_6") (pintype "output"))
    )
  )
)
